# Adafruit_nRF52840_Bluefruit_Feather_Expr.net
KiCad netlist of a schematic drawn in EAGLE
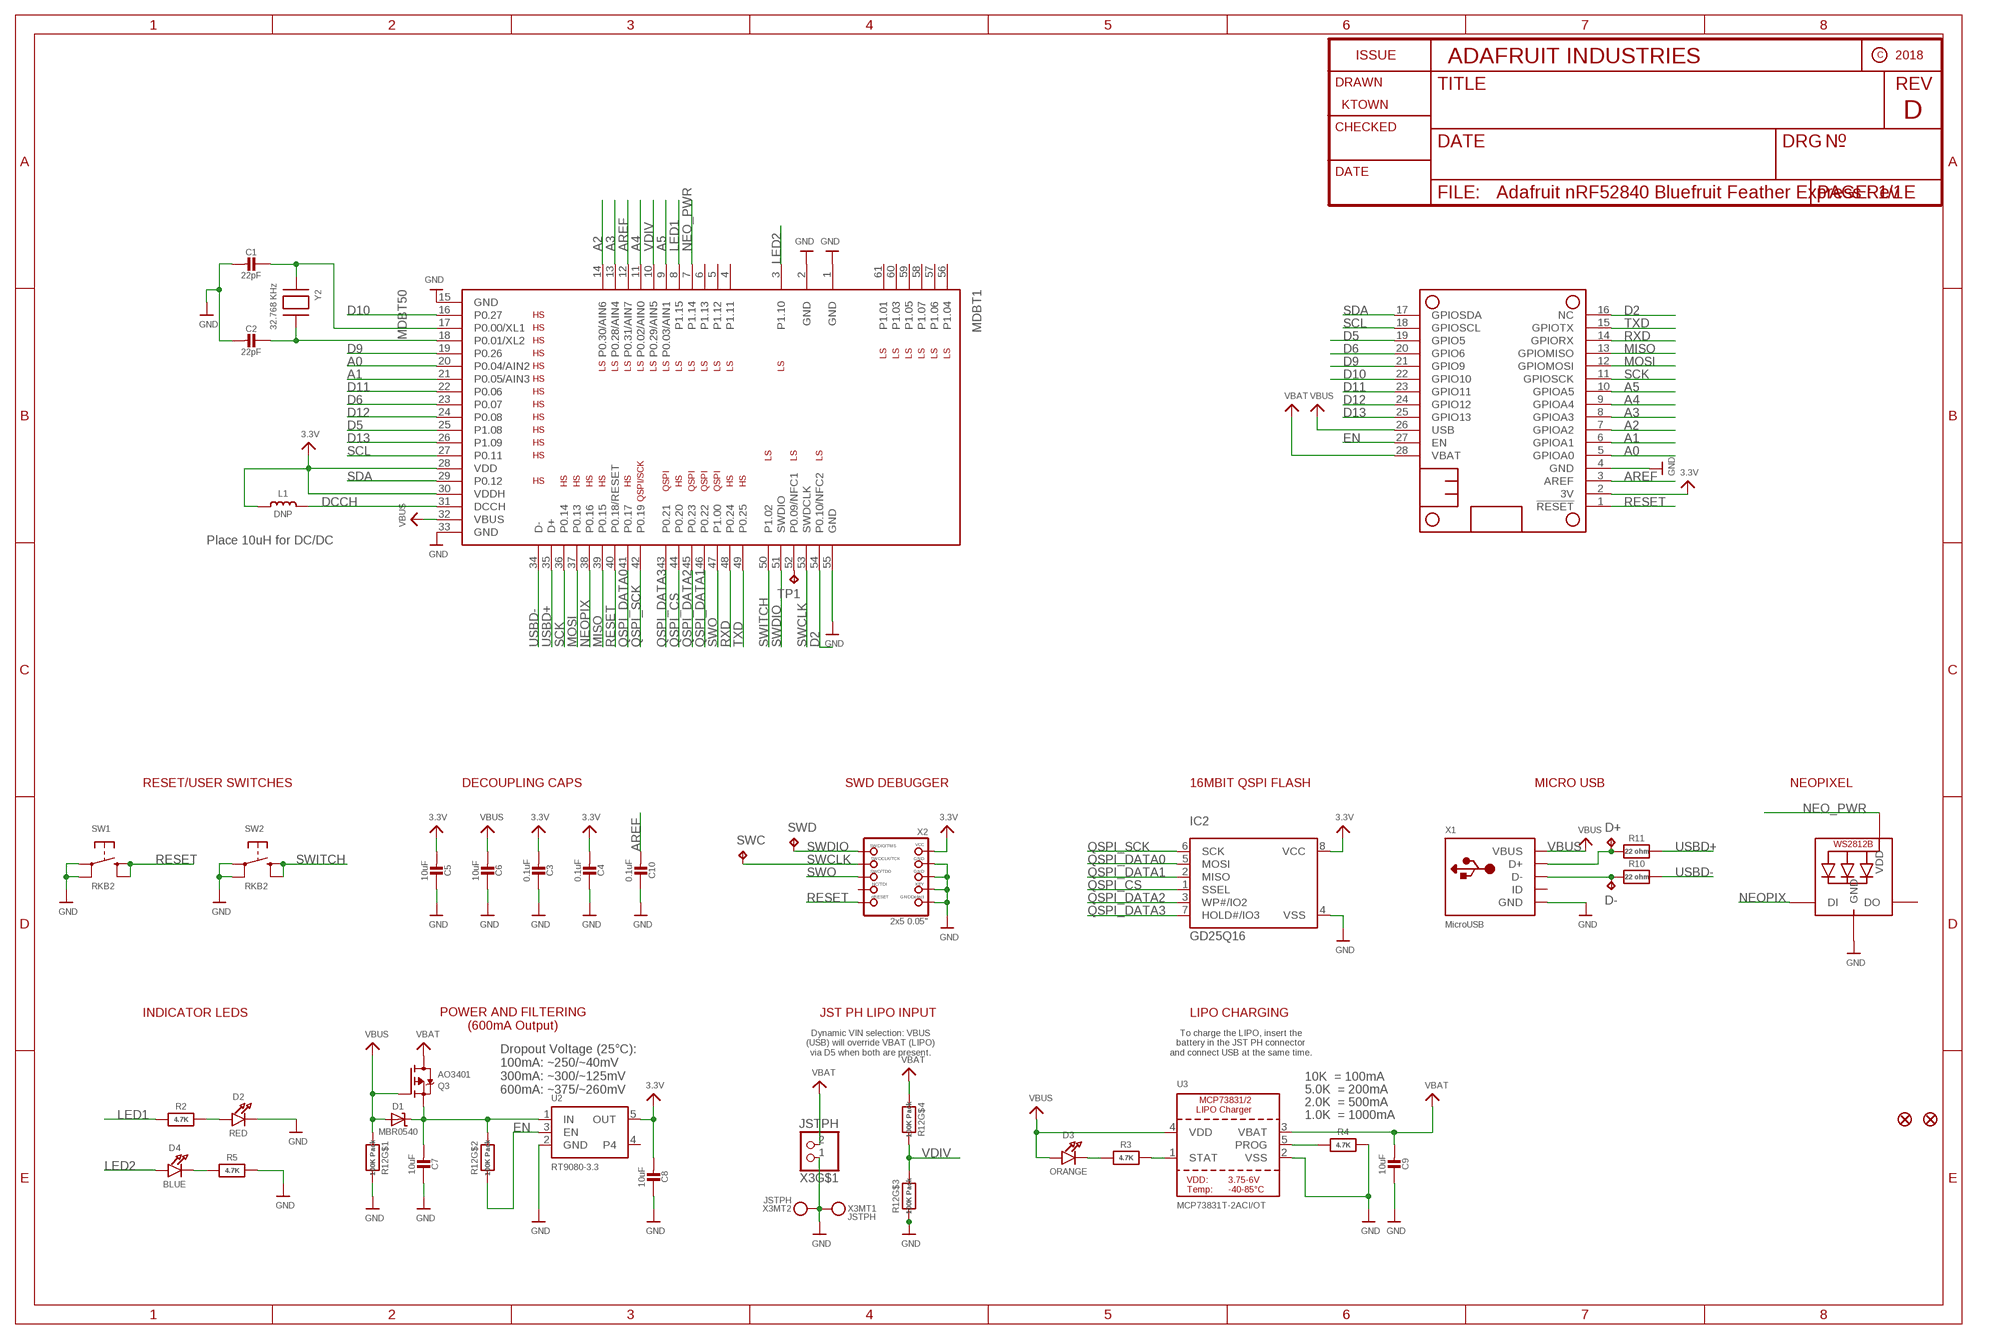
[diagram p0: schematic, sheet 1]

(export (version "E")
  (design (tool "Eeschema 10.0.6"))
  (components
    (comp (ref "C1")
      (value "22pF")
      (footprint "eagle-import:0603-NO")
      (libsource (lib "eagle-import") (part "CAP_CERAMIC0603_NO"))
    )
    (comp (ref "C2")
      (value "22pF")
      (footprint "eagle-import:0603-NO")
      (libsource (lib "eagle-import") (part "CAP_CERAMIC0603_NO"))
    )
    (comp (ref "C3")
      (value "0.1uF")
      (footprint "eagle-import:0603-NO")
      (libsource (lib "eagle-import") (part "CAP_CERAMIC0603_NO"))
    )
    (comp (ref "C4")
      (value "0.1uF")
      (footprint "eagle-import:0603-NO")
      (libsource (lib "eagle-import") (part "CAP_CERAMIC0603_NO"))
    )
    (comp (ref "C5")
      (value "10uF")
      (footprint "eagle-import:0805-NO")
      (libsource (lib "eagle-import") (part "CAP_CERAMIC0805-NOOUTLINE"))
    )
    (comp (ref "C6")
      (value "10uF")
      (footprint "eagle-import:0805-NO")
      (libsource (lib "eagle-import") (part "CAP_CERAMIC0805-NOOUTLINE"))
    )
    (comp (ref "C7")
      (value "10uF")
      (footprint "eagle-import:0805-NO")
      (libsource (lib "eagle-import") (part "CAP_CERAMIC0805-NOOUTLINE"))
    )
    (comp (ref "C8")
      (value "10uF")
      (footprint "eagle-import:0805-NO")
      (libsource (lib "eagle-import") (part "CAP_CERAMIC0805-NOOUTLINE"))
    )
    (comp (ref "C9")
      (value "10uF")
      (footprint "eagle-import:0805-NO")
      (libsource (lib "eagle-import") (part "CAP_CERAMIC0805-NOOUTLINE"))
    )
    (comp (ref "C10")
      (value "0.1uF")
      (footprint "eagle-import:0603-NO")
      (libsource (lib "eagle-import") (part "CAP_CERAMIC0603_NO"))
    )
    (comp (ref "D+")
      (value "TPTP10R")
      (footprint "eagle-import:TP10R")
      (libsource (lib "eagle-import") (part "TPTP10R"))
    )
    (comp (ref "D-")
      (value "TPTP10R")
      (footprint "eagle-import:TP10R")
      (libsource (lib "eagle-import") (part "TPTP10R"))
    )
    (comp (ref "D1")
      (value "MBR0540")
      (footprint "eagle-import:SOD-123")
      (libsource (lib "eagle-import") (part "DIODE-SCHOTTKYSOD-123"))
    )
    (comp (ref "D2")
      (value "RED")
      (footprint "eagle-import:CHIPLED_0603_NOOUTLINE")
      (libsource (lib "eagle-import") (part "LED0603_NOOUTLINE"))
    )
    (comp (ref "D3")
      (value "ORANGE")
      (footprint "eagle-import:CHIPLED_0603_NOOUTLINE")
      (libsource (lib "eagle-import") (part "LED0603_NOOUTLINE"))
    )
    (comp (ref "D4")
      (value "BLUE")
      (footprint "eagle-import:CHIPLED_0603_NOOUTLINE")
      (libsource (lib "eagle-import") (part "LED0603_NOOUTLINE"))
    )
    (comp (ref "FID1")
      (value "FIDUCIAL_1MM")
      (footprint "eagle-import:FIDUCIAL_1MM")
      (libsource (lib "eagle-import") (part "FIDUCIAL_1MM"))
    )
    (comp (ref "FID2")
      (value "FIDUCIAL_1MM")
      (footprint "eagle-import:FIDUCIAL_1MM")
      (libsource (lib "eagle-import") (part "FIDUCIAL_1MM"))
    )
    (comp (ref "IC2")
      (value "GD25Q16")
      (footprint "eagle-import:USON8")
      (libsource (lib "eagle-import") (part "SPIFLASH_8PINUX"))
    )
    (comp (ref "L1")
      (value "DNP")
      (footprint "eagle-import:_0805MP")
      (libsource (lib "eagle-import") (part "INDUCTOR_0805MP"))
    )
    (comp (ref "LED1")
      (value "WS2812B_3535FULL")
      (footprint "eagle-import:LED3535_FULLPADS")
      (libsource (lib "eagle-import") (part "WS2812B_3535FULL"))
    )
    (comp (ref "MDBT1")
      (value "MDBT50")
      (footprint "eagle-import:MDBT50")
      (libsource (lib "eagle-import") (part "MDBT50"))
    )
    (comp (ref "MS1")
      (value "FEATHERWING_NODIM")
      (footprint "eagle-import:FEATHERWING_NODIM")
      (libsource (lib "eagle-import") (part "FEATHERWING_NODIM"))
    )
    (comp (ref "Q3")
      (value "AO3401")
      (footprint "eagle-import:SOT23-R")
      (libsource (lib "eagle-import") (part "MOSFET-P"))
    )
    (comp (ref "R2")
      (value "4.7K")
      (footprint "eagle-import:0603-NO")
      (libsource (lib "eagle-import") (part "RESISTOR_0603_NOOUT"))
    )
    (comp (ref "R3")
      (value "4.7K")
      (footprint "eagle-import:0603-NO")
      (libsource (lib "eagle-import") (part "RESISTOR_0603_NOOUT"))
    )
    (comp (ref "R4")
      (value "4.7K")
      (footprint "eagle-import:0603-NO")
      (libsource (lib "eagle-import") (part "RESISTOR_0603_NOOUT"))
    )
    (comp (ref "R5")
      (value "4.7K")
      (footprint "eagle-import:0603-NO")
      (libsource (lib "eagle-import") (part "RESISTOR_0603_NOOUT"))
    )
    (comp (ref "R10")
      (value "22 ohm")
      (footprint "eagle-import:_0603MP")
      (libsource (lib "eagle-import") (part "RESISTOR_0603MP"))
    )
    (comp (ref "R11")
      (value "22 ohm")
      (footprint "eagle-import:_0603MP")
      (libsource (lib "eagle-import") (part "RESISTOR_0603MP"))
    )
    (comp (ref "R12")
      (value "100K Pack")
      (footprint "eagle-import:RESPACK_4X0603")
      (libsource (lib "eagle-import") (part "RESISTOR_4PACK"))
    )
    (comp (ref "SW1")
      (value "RKB2")
      (footprint "eagle-import:BTN_RKB2_4.6X2.8")
      (libsource (lib "eagle-import") (part "SWITCH_TACT_SMT_RKB2"))
    )
    (comp (ref "SW2")
      (value "RKB2")
      (footprint "eagle-import:BTN_RKB2_4.6X2.8")
      (libsource (lib "eagle-import") (part "SWITCH_TACT_SMT_RKB2"))
    )
    (comp (ref "SWC")
      (value "TPTP12R")
      (footprint "eagle-import:TP12R")
      (libsource (lib "eagle-import") (part "TPTP12R"))
    )
    (comp (ref "SWD")
      (value "TPTP12R")
      (footprint "eagle-import:TP12R")
      (libsource (lib "eagle-import") (part "TPTP12R"))
    )
    (comp (ref "TP1")
      (value "TPTP10R")
      (footprint "eagle-import:TP10R")
      (libsource (lib "eagle-import") (part "TPTP10R"))
    )
    (comp (ref "U2")
      (value "RT9080-3.3")
      (footprint "eagle-import:SOT23-5")
      (fields (field (name "JLC_ROTATION") "0"))
      (libsource (lib "eagle-import") (part "VREG_SOT23-5"))
    )
    (comp (ref "U3")
      (value "MCP73831T-2ACI/OT")
      (footprint "eagle-import:SOT23-5")
      (libsource (lib "eagle-import") (part "MCP73831/2"))
    )
    (comp (ref "X1")
      (value "MicroUSB")
      (footprint "eagle-import:4UCONN_20329_V2")
      (libsource (lib "eagle-import") (part "USB_MICRO_20329_V2"))
    )
    (comp (ref "X2")
      (value "2x5 0.05\"")
      (footprint "eagle-import:2X05_1.27MM_BOX_POSTS")
      (libsource (lib "eagle-import") (part "JTAG-CORTEXBOXPOSTS"))
    )
    (comp (ref "X3")
      (value "JSTPH")
      (footprint "eagle-import:JSTPH2_BATT")
      (libsource (lib "eagle-import") (part "CON_JST_PH_2PIN_MT_BATT"))
    )
    (comp (ref "Y2")
      (value "32.768 KHz")
      (footprint "eagle-import:XTAL3215")
      (libsource (lib "eagle-import") (part "XTAL-3.2X1.5"))
    )
  )
  (nets
    (net (code "1") (name "/A0") (class "Default")
      (node (ref "MDBT1") (pin "20") (pinfunction "P0.04/AIN2_20") (pintype "bidirectional"))
      (node (ref "MS1") (pin "5") (pinfunction "GPIOA0_5") (pintype "bidirectional"))
    )
    (net (code "2") (name "/A1") (class "Default")
      (node (ref "MDBT1") (pin "21") (pinfunction "P0.05/AIN3_21") (pintype "bidirectional"))
      (node (ref "MS1") (pin "6") (pinfunction "GPIOA1_6") (pintype "bidirectional"))
    )
    (net (code "3") (name "/A2") (class "Default")
      (node (ref "MDBT1") (pin "14") (pinfunction "P0.30/AIN6_14") (pintype "bidirectional"))
      (node (ref "MS1") (pin "7") (pinfunction "GPIOA2_7") (pintype "bidirectional"))
    )
    (net (code "4") (name "/A3") (class "Default")
      (node (ref "MDBT1") (pin "13") (pinfunction "P0.28/AIN4_13") (pintype "bidirectional"))
      (node (ref "MS1") (pin "8") (pinfunction "GPIOA3_8") (pintype "bidirectional"))
    )
    (net (code "5") (name "/A4") (class "Default")
      (node (ref "MDBT1") (pin "11") (pinfunction "P0.02/AIN0_11") (pintype "bidirectional"))
      (node (ref "MS1") (pin "9") (pinfunction "GPIOA4_9") (pintype "bidirectional"))
    )
    (net (code "6") (name "/A5") (class "Default")
      (node (ref "MDBT1") (pin "9") (pinfunction "P0.03/AIN1_9") (pintype "bidirectional"))
      (node (ref "MS1") (pin "10") (pinfunction "GPIOA5_10") (pintype "bidirectional"))
    )
    (net (code "7") (name "/AREF") (class "Default")
      (node (ref "C10") (pin "2") (pinfunction "2_2") (pintype "passive"))
      (node (ref "MDBT1") (pin "12") (pinfunction "P0.31/AIN7_12") (pintype "bidirectional"))
      (node (ref "MS1") (pin "3") (pinfunction "AREF_3") (pintype "passive"))
    )
    (net (code "8") (name "/D2") (class "Default")
      (node (ref "MDBT1") (pin "54") (pinfunction "P0.10/NFC2_54") (pintype "bidirectional"))
      (node (ref "MS1") (pin "16") (pinfunction "NC_16") (pintype "passive"))
    )
    (net (code "9") (name "/D5") (class "Default")
      (node (ref "MDBT1") (pin "25") (pinfunction "P1.08_25") (pintype "bidirectional"))
      (node (ref "MS1") (pin "19") (pinfunction "GPIO5_19") (pintype "bidirectional"))
    )
    (net (code "10") (name "/D6") (class "Default")
      (node (ref "MDBT1") (pin "23") (pinfunction "P0.07_23") (pintype "bidirectional"))
      (node (ref "MS1") (pin "20") (pinfunction "GPIO6_20") (pintype "bidirectional"))
    )
    (net (code "11") (name "/D9") (class "Default")
      (node (ref "MDBT1") (pin "19") (pinfunction "P0.26_19") (pintype "bidirectional"))
      (node (ref "MS1") (pin "21") (pinfunction "GPIO9_21") (pintype "bidirectional"))
    )
    (net (code "12") (name "/D10") (class "Default")
      (node (ref "MDBT1") (pin "16") (pinfunction "P0.27_16") (pintype "bidirectional"))
      (node (ref "MS1") (pin "22") (pinfunction "GPIO10_22") (pintype "bidirectional"))
    )
    (net (code "13") (name "/D11") (class "Default")
      (node (ref "MDBT1") (pin "22") (pinfunction "P0.06_22") (pintype "bidirectional"))
      (node (ref "MS1") (pin "23") (pinfunction "GPIO11_23") (pintype "bidirectional"))
    )
    (net (code "14") (name "/D12") (class "Default")
      (node (ref "MDBT1") (pin "24") (pinfunction "P0.08_24") (pintype "bidirectional"))
      (node (ref "MS1") (pin "24") (pinfunction "GPIO12_24") (pintype "bidirectional"))
    )
    (net (code "15") (name "/D13") (class "Default")
      (node (ref "MDBT1") (pin "26") (pinfunction "P1.09_26") (pintype "bidirectional"))
      (node (ref "MS1") (pin "25") (pinfunction "GPIO13_25") (pintype "bidirectional"))
    )
    (net (code "16") (name "/DCCH") (class "Default")
      (node (ref "L1") (pin "2") (pinfunction "2_2") (pintype "passive"))
      (node (ref "MDBT1") (pin "31") (pinfunction "DCCH_31") (pintype "bidirectional"))
    )
    (net (code "17") (name "/EN") (class "Default")
      (node (ref "MS1") (pin "27") (pinfunction "EN_27") (pintype "passive"))
      (node (ref "R12") (pin "2") (pinfunction "1_2") (pintype "passive"))
      (node (ref "U2") (pin "3") (pinfunction "EN_3") (pintype "input"))
    )
    (net (code "18") (name "/LED1") (class "Default")
      (node (ref "MDBT1") (pin "8") (pinfunction "P1.15_8") (pintype "bidirectional"))
      (node (ref "R2") (pin "1") (pinfunction "1_1") (pintype "passive"))
    )
    (net (code "19") (name "/LED2") (class "Default")
      (node (ref "D4") (pin "A") (pinfunction "A_A") (pintype "passive"))
      (node (ref "MDBT1") (pin "3") (pinfunction "P1.10_3") (pintype "bidirectional"))
    )
    (net (code "20") (name "/MISO") (class "Default")
      (node (ref "MDBT1") (pin "39") (pinfunction "P0.15_39") (pintype "bidirectional"))
      (node (ref "MS1") (pin "13") (pinfunction "GPIOMISO_13") (pintype "bidirectional"))
    )
    (net (code "21") (name "/MOSI") (class "Default")
      (node (ref "MDBT1") (pin "37") (pinfunction "P0.13_37") (pintype "bidirectional"))
      (node (ref "MS1") (pin "12") (pinfunction "GPIOMOSI_12") (pintype "bidirectional"))
    )
    (net (code "22") (name "/NEOPIX") (class "Default")
      (node (ref "LED1") (pin "1") (pinfunction "DI_1") (pintype "input"))
      (node (ref "MDBT1") (pin "38") (pinfunction "P0.16_38") (pintype "bidirectional"))
    )
    (net (code "23") (name "/NEO_PWR") (class "Default")
      (node (ref "LED1") (pin "2") (pinfunction "VDD_2") (pintype "power_in"))
      (node (ref "MDBT1") (pin "7") (pinfunction "P1.14_7") (pintype "bidirectional"))
    )
    (net (code "24") (name "/QSPI_CS") (class "Default")
      (node (ref "IC2") (pin "1") (pinfunction "SSEL_1") (pintype "bidirectional"))
      (node (ref "MDBT1") (pin "44") (pinfunction "P0.20_44") (pintype "bidirectional"))
    )
    (net (code "25") (name "/QSPI_DATA0") (class "Default")
      (node (ref "IC2") (pin "5") (pinfunction "MOSI_5") (pintype "bidirectional"))
      (node (ref "MDBT1") (pin "41") (pinfunction "P0.17_41") (pintype "bidirectional"))
    )
    (net (code "26") (name "/QSPI_DATA1") (class "Default")
      (node (ref "IC2") (pin "2") (pinfunction "MISO_2") (pintype "bidirectional"))
      (node (ref "MDBT1") (pin "46") (pinfunction "P0.22_46") (pintype "bidirectional"))
    )
    (net (code "27") (name "/QSPI_DATA2") (class "Default")
      (node (ref "IC2") (pin "3") (pinfunction "WP#/IO2_3") (pintype "bidirectional"))
      (node (ref "MDBT1") (pin "45") (pinfunction "P0.23_45") (pintype "bidirectional"))
    )
    (net (code "28") (name "/QSPI_DATA3") (class "Default")
      (node (ref "IC2") (pin "7") (pinfunction "HOLD#/IO3_7") (pintype "bidirectional"))
      (node (ref "MDBT1") (pin "43") (pinfunction "P0.21_43") (pintype "bidirectional"))
    )
    (net (code "29") (name "/QSPI_SCK") (class "Default")
      (node (ref "IC2") (pin "6") (pinfunction "SCK_6") (pintype "bidirectional"))
      (node (ref "MDBT1") (pin "42") (pinfunction "P0.19_42") (pintype "bidirectional"))
    )
    (net (code "30") (name "/RESET") (class "Default")
      (node (ref "MDBT1") (pin "40") (pinfunction "P0.18/RESET_40") (pintype "bidirectional"))
      (node (ref "MS1") (pin "1") (pinfunction "~{RESET}_1") (pintype "input"))
      (node (ref "SW1") (pin "B") (pinfunction "S_B") (pintype "passive"))
      (node (ref "SW1") (pin "B'") (pinfunction "S1_B'") (pintype "passive"))
      (node (ref "X2") (pin "10") (pinfunction "NRESET_10") (pintype "bidirectional"))
    )
    (net (code "31") (name "/RXD") (class "Default")
      (node (ref "MDBT1") (pin "48") (pinfunction "P0.24_48") (pintype "bidirectional"))
      (node (ref "MS1") (pin "14") (pinfunction "GPIORX_14") (pintype "bidirectional"))
    )
    (net (code "32") (name "/SCK") (class "Default")
      (node (ref "MDBT1") (pin "36") (pinfunction "P0.14_36") (pintype "bidirectional"))
      (node (ref "MS1") (pin "11") (pinfunction "GPIOSCK_11") (pintype "bidirectional"))
    )
    (net (code "33") (name "/SCL") (class "Default")
      (node (ref "MDBT1") (pin "27") (pinfunction "P0.11_27") (pintype "bidirectional"))
      (node (ref "MS1") (pin "18") (pinfunction "GPIOSCL_18") (pintype "bidirectional"))
    )
    (net (code "34") (name "/SDA") (class "Default")
      (node (ref "MDBT1") (pin "29") (pinfunction "P0.12_29") (pintype "bidirectional"))
      (node (ref "MS1") (pin "17") (pinfunction "GPIOSDA_17") (pintype "bidirectional"))
    )
    (net (code "35") (name "/SWCLK") (class "Default")
      (node (ref "MDBT1") (pin "53") (pinfunction "SWDCLK_53") (pintype "bidirectional"))
      (node (ref "SWC") (pin "TP") (pinfunction "TP_TP") (pintype "input"))
      (node (ref "X2") (pin "4") (pinfunction "SWDCLK_4") (pintype "bidirectional"))
    )
    (net (code "36") (name "/SWDIO") (class "Default")
      (node (ref "MDBT1") (pin "51") (pinfunction "SWDIO_51") (pintype "bidirectional"))
      (node (ref "SWD") (pin "TP") (pinfunction "TP_TP") (pintype "input"))
      (node (ref "X2") (pin "2") (pinfunction "SWDIO_2") (pintype "bidirectional"))
    )
    (net (code "37") (name "/SWITCH") (class "Default")
      (node (ref "MDBT1") (pin "50") (pinfunction "P1.02_50") (pintype "bidirectional"))
      (node (ref "SW2") (pin "B") (pinfunction "S_B") (pintype "passive"))
      (node (ref "SW2") (pin "B'") (pinfunction "S1_B'") (pintype "passive"))
    )
    (net (code "38") (name "/SWO") (class "Default")
      (node (ref "MDBT1") (pin "47") (pinfunction "P1.00_47") (pintype "bidirectional"))
      (node (ref "X2") (pin "6") (pinfunction "SWO_6") (pintype "bidirectional"))
    )
    (net (code "39") (name "/TXD") (class "Default")
      (node (ref "MDBT1") (pin "49") (pinfunction "P0.25_49") (pintype "bidirectional"))
      (node (ref "MS1") (pin "15") (pinfunction "GPIOTX_15") (pintype "bidirectional"))
    )
    (net (code "40") (name "/USBD+") (class "Default")
      (node (ref "MDBT1") (pin "35") (pinfunction "D+_35") (pintype "bidirectional"))
      (node (ref "R11") (pin "2") (pinfunction "2_2") (pintype "passive"))
    )
    (net (code "41") (name "/USBD-") (class "Default")
      (node (ref "MDBT1") (pin "34") (pinfunction "D-_34") (pintype "bidirectional"))
      (node (ref "R10") (pin "2") (pinfunction "2_2") (pintype "passive"))
    )
    (net (code "42") (name "/VDIV") (class "Default")
      (node (ref "MDBT1") (pin "10") (pinfunction "P0.29/AIN5_10") (pintype "bidirectional"))
      (node (ref "R12") (pin "5") (pinfunction "2_5") (pintype "passive"))
      (node (ref "R12") (pin "6") (pinfunction "2_6") (pintype "passive"))
    )
    (net (code "43") (name "3.3V") (class "Default")
      (node (ref "C3") (pin "2") (pinfunction "2_2") (pintype "passive"))
      (node (ref "C4") (pin "2") (pinfunction "2_2") (pintype "passive"))
      (node (ref "C5") (pin "2") (pinfunction "2_2") (pintype "passive"))
      (node (ref "C8") (pin "2") (pinfunction "2_2") (pintype "passive"))
      (node (ref "IC2") (pin "8") (pinfunction "VCC_8") (pintype "bidirectional"))
      (node (ref "L1") (pin "1") (pinfunction "1_1") (pintype "passive"))
      (node (ref "MDBT1") (pin "28") (pinfunction "VDD_28") (pintype "bidirectional"))
      (node (ref "MDBT1") (pin "30") (pinfunction "VDDH_30") (pintype "bidirectional"))
      (node (ref "MS1") (pin "2") (pinfunction "3V_2") (pintype "power_in"))
      (node (ref "U2") (pin "5") (pinfunction "OUT_5") (pintype "power_in"))
      (node (ref "X2") (pin "1") (pinfunction "VCC_1") (pintype "power_in"))
    )
    (net (code "44") (name "GND") (class "Default")
      (node (ref "C1") (pin "2") (pinfunction "2_2") (pintype "passive"))
      (node (ref "C10") (pin "1") (pinfunction "1_1") (pintype "passive"))
      (node (ref "C2") (pin "2") (pinfunction "2_2") (pintype "passive"))
      (node (ref "C3") (pin "1") (pinfunction "1_1") (pintype "passive"))
      (node (ref "C4") (pin "1") (pinfunction "1_1") (pintype "passive"))
      (node (ref "C5") (pin "1") (pinfunction "1_1") (pintype "passive"))
      (node (ref "C6") (pin "1") (pinfunction "1_1") (pintype "passive"))
      (node (ref "C7") (pin "1") (pinfunction "1_1") (pintype "passive"))
      (node (ref "C8") (pin "1") (pinfunction "1_1") (pintype "passive"))
      (node (ref "C9") (pin "1") (pinfunction "1_1") (pintype "passive"))
      (node (ref "D2") (pin "C") (pinfunction "C_C") (pintype "passive"))
      (node (ref "IC2") (pin "4") (pinfunction "VSS_4") (pintype "bidirectional"))
      (node (ref "LED1") (pin "4") (pinfunction "GND_4") (pintype "power_in"))
      (node (ref "MDBT1") (pin "1") (pinfunction "GND_1") (pintype "bidirectional"))
      (node (ref "MDBT1") (pin "15") (pinfunction "GND_15") (pintype "bidirectional"))
      (node (ref "MDBT1") (pin "2") (pinfunction "GND_2") (pintype "bidirectional"))
      (node (ref "MDBT1") (pin "33") (pinfunction "GND_33") (pintype "bidirectional"))
      (node (ref "MDBT1") (pin "55") (pinfunction "GND_55") (pintype "bidirectional"))
      (node (ref "MS1") (pin "4") (pinfunction "GND_4") (pintype "power_in"))
      (node (ref "R12") (pin "3") (pinfunction "1_3") (pintype "passive"))
      (node (ref "R12") (pin "8") (pinfunction "2_8") (pintype "passive"))
      (node (ref "R4") (pin "2") (pinfunction "2_2") (pintype "passive"))
      (node (ref "R5") (pin "2") (pinfunction "2_2") (pintype "passive"))
      (node (ref "SW1") (pin "A") (pinfunction "P_A") (pintype "passive"))
      (node (ref "SW1") (pin "A'") (pinfunction "P1_A'") (pintype "passive"))
      (node (ref "SW2") (pin "A") (pinfunction "P_A") (pintype "passive"))
      (node (ref "SW2") (pin "A'") (pinfunction "P1_A'") (pintype "passive"))
      (node (ref "U2") (pin "2") (pinfunction "GND_2") (pintype "power_in"))
      (node (ref "U3") (pin "2") (pinfunction "VSS_2") (pintype "power_in"))
      (node (ref "X1") (pin "BASE@1") (pinfunction "GND_BASE@1") (pintype "power_in"))
      (node (ref "X1") (pin "BASE@2") (pinfunction "GND_BASE@2") (pintype "power_in"))
      (node (ref "X1") (pin "GND") (pinfunction "GND_GND") (pintype "power_in"))
      (node (ref "X1") (pin "SPRT@1") (pinfunction "GND_SPRT@1") (pintype "power_in"))
      (node (ref "X1") (pin "SPRT@2") (pinfunction "GND_SPRT@2") (pintype "power_in"))
      (node (ref "X1") (pin "SPRT@3") (pinfunction "GND_SPRT@3") (pintype "power_in"))
      (node (ref "X1") (pin "SPRT@4") (pinfunction "GND_SPRT@4") (pintype "power_in"))
      (node (ref "X2") (pin "3") (pinfunction "GND_3") (pintype "power_in"))
      (node (ref "X2") (pin "5") (pinfunction "GND_5") (pintype "power_in"))
      (node (ref "X2") (pin "7") (pinfunction "KEY_7") (pintype "bidirectional"))
      (node (ref "X2") (pin "9") (pinfunction "GNDDETECT_9") (pintype "bidirectional"))
      (node (ref "X3") (pin "1") (pinfunction "1_1") (pintype "passive"))
      (node (ref "X3") (pin "NC1") (pinfunction "P$1_NC1") (pintype "bidirectional"))
      (node (ref "X3") (pin "NC2") (pinfunction "P$1_NC2") (pintype "bidirectional"))
    )
    (net (code "45") (name "Net-(D+-PadTP)") (class "Default")
      (node (ref "D+") (pin "TP") (pinfunction "TP_TP") (pintype "input"))
      (node (ref "R11") (pin "1") (pinfunction "1_1") (pintype "passive"))
      (node (ref "X1") (pin "D+") (pinfunction "D+_D+") (pintype "bidirectional"))
    )
    (net (code "46") (name "Net-(D--PadTP)") (class "Default")
      (node (ref "D-") (pin "TP") (pinfunction "TP_TP") (pintype "input"))
      (node (ref "R10") (pin "1") (pinfunction "1_1") (pintype "passive"))
      (node (ref "X1") (pin "D-") (pinfunction "D-_D-") (pintype "bidirectional"))
    )
    (net (code "47") (name "Net-(D2-PadA)") (class "Default")
      (node (ref "D2") (pin "A") (pinfunction "A_A") (pintype "passive"))
      (node (ref "R2") (pin "2") (pinfunction "2_2") (pintype "passive"))
    )
    (net (code "48") (name "Net-(D3-PadC)") (class "Default")
      (node (ref "D3") (pin "C") (pinfunction "C_C") (pintype "passive"))
      (node (ref "R3") (pin "1") (pinfunction "1_1") (pintype "passive"))
    )
    (net (code "49") (name "Net-(D4-PadC)") (class "Default")
      (node (ref "D4") (pin "C") (pinfunction "C_C") (pintype "passive"))
      (node (ref "R5") (pin "1") (pinfunction "1_1") (pintype "passive"))
    )
    (net (code "50") (name "Net-(MDBT1-P0.00{slash}XL1)") (class "Default")
      (node (ref "C1") (pin "1") (pinfunction "1_1") (pintype "passive"))
      (node (ref "MDBT1") (pin "17") (pinfunction "P0.00/XL1_17") (pintype "bidirectional"))
      (node (ref "Y2") (pin "P$1") (pinfunction "P$1_P$1") (pintype "bidirectional"))
    )
    (net (code "51") (name "Net-(MDBT1-P0.01{slash}XL2)") (class "Default")
      (node (ref "C2") (pin "1") (pinfunction "1_1") (pintype "passive"))
      (node (ref "MDBT1") (pin "18") (pinfunction "P0.01/XL2_18") (pintype "bidirectional"))
      (node (ref "Y2") (pin "P$2") (pinfunction "P$2_P$2") (pintype "bidirectional"))
    )
    (net (code "52") (name "Net-(MDBT1-P0.09{slash}NFC1)") (class "Default")
      (node (ref "MDBT1") (pin "52") (pinfunction "P0.09/NFC1_52") (pintype "bidirectional"))
      (node (ref "TP1") (pin "TP") (pinfunction "TP_TP") (pintype "input"))
    )
    (net (code "53") (name "Net-(Q3-S)") (class "Default")
      (node (ref "C7") (pin "2") (pinfunction "2_2") (pintype "passive"))
      (node (ref "D1") (pin "C") (pinfunction "C_C") (pintype "passive"))
      (node (ref "Q3") (pin "2") (pinfunction "S_2") (pintype "passive"))
      (node (ref "R12") (pin "7") (pinfunction "2_7") (pintype "passive"))
      (node (ref "U2") (pin "1") (pinfunction "IN_1") (pintype "power_in"))
    )
    (net (code "54") (name "Net-(U3-PROG)") (class "Default")
      (node (ref "R4") (pin "1") (pinfunction "1_1") (pintype "passive"))
      (node (ref "U3") (pin "5") (pinfunction "PROG_5") (pintype "input"))
    )
    (net (code "55") (name "Net-(U3-STAT)") (class "Default")
      (node (ref "R3") (pin "2") (pinfunction "2_2") (pintype "passive"))
      (node (ref "U3") (pin "1") (pinfunction "STAT_1") (pintype "output"))
    )
    (net (code "56") (name "VBAT") (class "Default")
      (node (ref "C9") (pin "2") (pinfunction "2_2") (pintype "passive"))
      (node (ref "MS1") (pin "28") (pinfunction "VBAT_28") (pintype "power_in"))
      (node (ref "Q3") (pin "3") (pinfunction "D_3") (pintype "passive"))
      (node (ref "R12") (pin "4") (pinfunction "1_4") (pintype "passive"))
      (node (ref "U3") (pin "3") (pinfunction "VBAT_3") (pintype "power_in"))
      (node (ref "X3") (pin "2") (pinfunction "2_2") (pintype "passive"))
    )
    (net (code "57") (name "VBUS") (class "Default")
      (node (ref "C6") (pin "2") (pinfunction "2_2") (pintype "passive"))
      (node (ref "D1") (pin "A") (pinfunction "A_A") (pintype "passive"))
      (node (ref "D3") (pin "A") (pinfunction "A_A") (pintype "passive"))
      (node (ref "MDBT1") (pin "32") (pinfunction "VBUS_32") (pintype "bidirectional"))
      (node (ref "MS1") (pin "26") (pinfunction "USB_26") (pintype "power_in"))
      (node (ref "Q3") (pin "1") (pinfunction "G_1") (pintype "passive"))
      (node (ref "R12") (pin "1") (pinfunction "1_1") (pintype "passive"))
      (node (ref "U3") (pin "4") (pinfunction "VDD_4") (pintype "power_in"))
      (node (ref "X1") (pin "VBUS") (pinfunction "VBUS_VBUS") (pintype "power_in"))
    )
    (net (code "58") (name "unconnected-(LED1-DO-Pad3)") (class "Default")
      (node (ref "LED1") (pin "3") (pinfunction "DO_3") (pintype "output"))
    )
    (net (code "59") (name "unconnected-(MDBT1-P1.01-Pad61)") (class "Default")
      (node (ref "MDBT1") (pin "61") (pinfunction "P1.01_61") (pintype "bidirectional"))
    )
    (net (code "60") (name "unconnected-(MDBT1-P1.03-Pad60)") (class "Default")
      (node (ref "MDBT1") (pin "60") (pinfunction "P1.03_60") (pintype "bidirectional"))
    )
    (net (code "61") (name "unconnected-(MDBT1-P1.04-Pad56)") (class "Default")
      (node (ref "MDBT1") (pin "56") (pinfunction "P1.04_56") (pintype "bidirectional"))
    )
    (net (code "62") (name "unconnected-(MDBT1-P1.05-Pad59)") (class "Default")
      (node (ref "MDBT1") (pin "59") (pinfunction "P1.05_59") (pintype "bidirectional"))
    )
    (net (code "63") (name "unconnected-(MDBT1-P1.06-Pad57)") (class "Default")
      (node (ref "MDBT1") (pin "57") (pinfunction "P1.06_57") (pintype "bidirectional"))
    )
    (net (code "64") (name "unconnected-(MDBT1-P1.07-Pad58)") (class "Default")
      (node (ref "MDBT1") (pin "58") (pinfunction "P1.07_58") (pintype "bidirectional"))
    )
    (net (code "65") (name "unconnected-(MDBT1-P1.11-Pad4)") (class "Default")
      (node (ref "MDBT1") (pin "4") (pinfunction "P1.11_4") (pintype "bidirectional"))
    )
    (net (code "66") (name "unconnected-(MDBT1-P1.12-Pad5)") (class "Default")
      (node (ref "MDBT1") (pin "5") (pinfunction "P1.12_5") (pintype "bidirectional"))
    )
    (net (code "67") (name "unconnected-(MDBT1-P1.13-Pad6)") (class "Default")
      (node (ref "MDBT1") (pin "6") (pinfunction "P1.13_6") (pintype "bidirectional"))
    )
    (net (code "68") (name "unconnected-(U2-P4-Pad4)") (class "Default")
      (node (ref "U2") (pin "4") (pinfunction "P4_4") (pintype "bidirectional"))
    )
    (net (code "69") (name "unconnected-(X1-PadID)") (class "Default")
      (node (ref "X1") (pin "ID") (pinfunction "ID_ID") (pintype "bidirectional"))
    )
    (net (code "70") (name "unconnected-(X2-TDI-Pad8)") (class "Default")
      (node (ref "X2") (pin "8") (pinfunction "TDI_8") (pintype "bidirectional"))
    )
  )
)
